# 04_-_BATTERIES_WITH_PROTECTION.net
KiCad netlist of a schematic drawn in Altium Designer
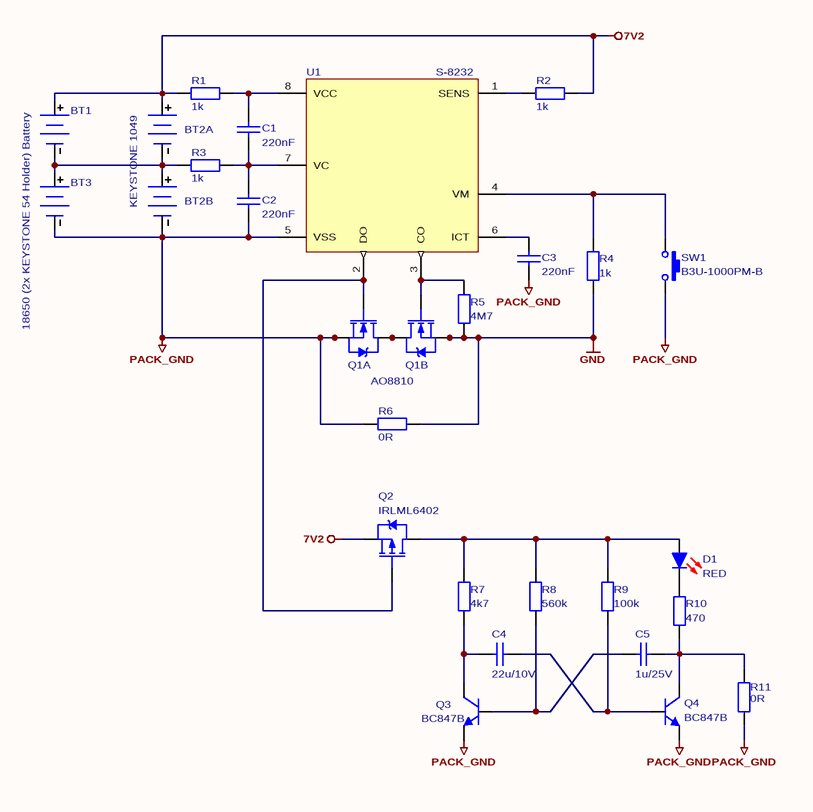
[diagram p0: [04] - BATTERIES WITH PROTECTION.SchDoc]

(export (version "E")
  (design (tool "Eeschema 10.0.6"))
  (components
    (comp (ref "BT1")
      (value "18650 (2x KEYSTONE 54 Holder) Battery")
      (footprint "KEYSTONE_54_W_18650")
      (fields (field (name "PUBLISHER") "Altium Limited"))
      (libsource (lib "baterries_and_accus") (part "18650"))
    )
    (comp (ref "BT2")
      (value "KEYSTONE 1049")
      (footprint "KEYSTONE_1049")
      (description "2x 18650 LiPo Acu in the KEYSTONE 1049 Holder")
      (libsource (lib "baterries_and_accus") (part "Keystone 1049"))
    )
    (comp (ref "BT3")
      (value "18650 (2x KEYSTONE 54 Holder) Battery")
      (footprint "KEYSTONE_54_W_18650")
      (fields (field (name "PUBLISHER") "Altium Limited"))
      (libsource (lib "baterries_and_accus") (part "18650"))
    )
    (comp (ref "C1")
      (value "220nF")
      (footprint "C0805")
      (description "Capacitor")
      (libsource (lib "capacitors") (part "Cap"))
    )
    (comp (ref "C2")
      (value "220nF")
      (footprint "C0805")
      (description "Capacitor")
      (libsource (lib "capacitors") (part "Cap"))
    )
    (comp (ref "C3")
      (value "220nF")
      (footprint "C0805")
      (description "Capacitor")
      (libsource (lib "capacitors") (part "Cap"))
    )
    (comp (ref "C4")
      (value "22u/10V")
      (footprint "C0805")
      (description "Capacitor")
      (libsource (lib "capacitors") (part "Cap"))
    )
    (comp (ref "C5")
      (value "1u/25V")
      (footprint "C0805")
      (description "Capacitor")
      (libsource (lib "capacitors") (part "Cap"))
    )
    (comp (ref "D1")
      (value "RED")
      (footprint "LED0805R")
      (description "RED LED")
      (libsource (lib "leds") (part "LED_RED"))
    )
    (comp (ref "Q1")
      (value "AO8810")
      (footprint "TSSOP8")
      (description "Dual Common Drain N-Channel MOSFET: Vds=20V, Rdson<20mR@4,5V, Id=7A")
      (libsource (lib "transistors_mos") (part "AO8810"))
    )
    (comp (ref "Q2")
      (value "IRLML6402")
      (footprint "SOT-23")
      (description "P-Channel; -20V, -3.7A, 1.3W; HEXFET Power MOS-FET")
      (libsource (lib "transistors_mos") (part "IRLML6402"))
    )
    (comp (ref "Q3")
      (value "BC847B")
      (footprint "SOT-23")
      (description "NPN General Purpose Transistor (VCE=45V, IC=100mA, HFE=200-450)")
      (libsource (lib "transistors_bjt") (part "BC847B"))
    )
    (comp (ref "Q4")
      (value "BC847B")
      (footprint "SOT-23")
      (description "NPN General Purpose Transistor (VCE=45V, IC=100mA, HFE=200-450)")
      (libsource (lib "transistors_bjt") (part "BC847B"))
    )
    (comp (ref "R1")
      (value "1k")
      (footprint "R0805")
      (description "Resistor")
      (libsource (lib "") (part "Res_1"))
    )
    (comp (ref "R2")
      (value "1k")
      (footprint "R0805")
      (description "Resistor")
      (libsource (lib "") (part "Res_1"))
    )
    (comp (ref "R3")
      (value "1k")
      (footprint "R0805")
      (description "Resistor")
      (libsource (lib "") (part "Res_1"))
    )
    (comp (ref "R4")
      (value "1k")
      (footprint "R0805")
      (description "Resistor")
      (libsource (lib "resistors") (part "Res"))
    )
    (comp (ref "R5")
      (value "4M7")
      (footprint "R0805")
      (description "Resistor")
      (libsource (lib "resistors") (part "Res"))
    )
    (comp (ref "R6")
      (value "0R")
      (footprint "R0805")
      (description "Resistor")
      (libsource (lib "") (part "Res_3"))
    )
    (comp (ref "R7")
      (value "4k7")
      (footprint "R0805")
      (description "Resistor")
      (libsource (lib "resistors") (part "Res"))
    )
    (comp (ref "R8")
      (value "560k")
      (footprint "R0805")
      (description "Resistor")
      (libsource (lib "resistors") (part "Res"))
    )
    (comp (ref "R9")
      (value "100k")
      (footprint "R0805")
      (description "Resistor")
      (libsource (lib "resistors") (part "Res"))
    )
    (comp (ref "R10")
      (value "470")
      (footprint "R0805")
      (description "Resistor")
      (libsource (lib "resistors") (part "Res"))
    )
    (comp (ref "R11")
      (value "0R")
      (footprint "R0805")
      (description "Resistor")
      (libsource (lib "") (part "Res_2"))
    )
    (comp (ref "SW1")
      (value "B3U-1000PM-B")
      (footprint "B3U-1000PM-B")
      (description "OMRON Ultra-small Tactile Switch - 12V/50mA")
      (libsource (lib "microswitches") (part "B3U-1000PM-B"))
    )
    (comp (ref "U1")
      (value "S-8232")
      (footprint "TSSOP8")
      (description "Battery Protection IC For 2-Serial-Cell Pack")
      (libsource (lib "protection_circuits") (part "S-8232"))
    )
  )
  (nets
    (net (code "1") (name "7V2") (class "Default")
      (node (ref "BT1") (pin "1") (pinfunction "+_1") (pintype "passive"))
      (node (ref "BT2") (pin "1") (pinfunction "+_1") (pintype "passive"))
      (node (ref "Q2") (pin "2") (pinfunction "S_2") (pintype "passive"))
      (node (ref "R1") (pin "1") (pinfunction "1_1") (pintype "passive"))
      (node (ref "R2") (pin "2") (pinfunction "2_2") (pintype "passive"))
    )
    (net (code "2") (name "GND") (class "Default")
      (node (ref "Q1") (pin "6") (pinfunction "S2_6") (pintype "passive"))
      (node (ref "Q1") (pin "7") (pinfunction "S2_7") (pintype "passive"))
      (node (ref "R4") (pin "2") (pinfunction "2_2") (pintype "passive"))
      (node (ref "R5") (pin "2") (pinfunction "2_2") (pintype "passive"))
      (node (ref "R6") (pin "1") (pinfunction "1_1") (pintype "passive"))
    )
    (net (code "3") (name "Net-(BT1--)") (class "Default")
      (node (ref "BT1") (pin "2") (pinfunction "-_2") (pintype "passive"))
      (node (ref "BT2") (pin "2") (pinfunction "-_2") (pintype "passive"))
      (node (ref "BT2") (pin "4") (pinfunction "+_4") (pintype "passive"))
      (node (ref "BT3") (pin "1") (pinfunction "+_1") (pintype "passive"))
      (node (ref "R3") (pin "1") (pinfunction "1_1") (pintype "passive"))
    )
    (net (code "4") (name "Net-(D1-A)") (class "Default")
      (node (ref "D1") (pin "1") (pinfunction "A_1") (pintype "passive"))
      (node (ref "Q2") (pin "3") (pinfunction "D_3") (pintype "passive"))
      (node (ref "R7") (pin "1") (pinfunction "1_1") (pintype "passive"))
      (node (ref "R8") (pin "1") (pinfunction "1_1") (pintype "passive"))
      (node (ref "R9") (pin "1") (pinfunction "1_1") (pintype "passive"))
    )
    (net (code "5") (name "Net-(D1-K)") (class "Default")
      (node (ref "D1") (pin "2") (pinfunction "K_2") (pintype "passive"))
      (node (ref "R10") (pin "1") (pinfunction "1_1") (pintype "passive"))
    )
    (net (code "6") (name "Net-(Q1A-D1{slash}D2)") (class "Default")
      (node (ref "Q1") (pin "1") (pinfunction "D1/D2_1") (pintype "passive"))
      (node (ref "Q1") (pin "8") (pinfunction "D1/D3_8") (pintype "passive"))
    )
    (net (code "7") (name "Net-(Q1A-G1)") (class "Default")
      (node (ref "Q1") (pin "4") (pinfunction "G1_4") (pintype "passive"))
      (node (ref "Q2") (pin "1") (pinfunction "G_1") (pintype "passive"))
      (node (ref "U1") (pin "2") (pinfunction "DO_2") (pintype "output"))
    )
    (net (code "8") (name "Net-(Q1B-G2)") (class "Default")
      (node (ref "Q1") (pin "5") (pinfunction "G2_5") (pintype "passive"))
      (node (ref "R5") (pin "1") (pinfunction "1_1") (pintype "passive"))
      (node (ref "U1") (pin "3") (pinfunction "CO_3") (pintype "output"))
    )
    (net (code "9") (name "Net-(Q3-B)") (class "Default")
      (node (ref "C5") (pin "1") (pinfunction "1_1") (pintype "passive"))
      (node (ref "Q3") (pin "1") (pinfunction "B_1") (pintype "passive"))
      (node (ref "R8") (pin "2") (pinfunction "2_2") (pintype "passive"))
    )
    (net (code "10") (name "Net-(Q3-C)") (class "Default")
      (node (ref "C4") (pin "1") (pinfunction "1_1") (pintype "passive"))
      (node (ref "Q3") (pin "3") (pinfunction "C_3") (pintype "passive"))
      (node (ref "R7") (pin "2") (pinfunction "2_2") (pintype "passive"))
    )
    (net (code "11") (name "Net-(Q4-B)") (class "Default")
      (node (ref "C4") (pin "2") (pinfunction "2_2") (pintype "passive"))
      (node (ref "Q4") (pin "1") (pinfunction "B_1") (pintype "passive"))
      (node (ref "R9") (pin "2") (pinfunction "2_2") (pintype "passive"))
    )
    (net (code "12") (name "Net-(Q4-C)") (class "Default")
      (node (ref "C5") (pin "2") (pinfunction "2_2") (pintype "passive"))
      (node (ref "Q4") (pin "3") (pinfunction "C_3") (pintype "passive"))
      (node (ref "R10") (pin "2") (pinfunction "2_2") (pintype "passive"))
      (node (ref "R11") (pin "2") (pinfunction "2_2") (pintype "passive"))
    )
    (net (code "13") (name "Net-(U1-ICT)") (class "Default")
      (node (ref "C3") (pin "2") (pinfunction "2_2") (pintype "passive"))
      (node (ref "U1") (pin "6") (pinfunction "ICT_6") (pintype "passive"))
    )
    (net (code "14") (name "Net-(U1-SENS)") (class "Default")
      (node (ref "R2") (pin "1") (pinfunction "1_1") (pintype "passive"))
      (node (ref "U1") (pin "1") (pinfunction "SENS_1") (pintype "passive"))
    )
    (net (code "15") (name "Net-(U1-VC)") (class "Default")
      (node (ref "C1") (pin "1") (pinfunction "1_1") (pintype "passive"))
      (node (ref "C2") (pin "2") (pinfunction "2_2") (pintype "passive"))
      (node (ref "R3") (pin "2") (pinfunction "2_2") (pintype "passive"))
      (node (ref "U1") (pin "7") (pinfunction "VC_7") (pintype "passive"))
    )
    (net (code "16") (name "Net-(U1-VCC)") (class "Default")
      (node (ref "C1") (pin "2") (pinfunction "2_2") (pintype "passive"))
      (node (ref "R1") (pin "2") (pinfunction "2_2") (pintype "passive"))
      (node (ref "U1") (pin "8") (pinfunction "VCC_8") (pintype "passive"))
    )
    (net (code "17") (name "Net-(U1-VM)") (class "Default")
      (node (ref "R4") (pin "1") (pinfunction "1_1") (pintype "passive"))
      (node (ref "SW1") (pin "1") (pinfunction "1_1") (pintype "passive"))
      (node (ref "U1") (pin "4") (pinfunction "VM_4") (pintype "passive"))
    )
    (net (code "18") (name "PACK_GND") (class "Default")
      (node (ref "BT2") (pin "3") (pinfunction "-_3") (pintype "passive"))
      (node (ref "BT3") (pin "2") (pinfunction "-_2") (pintype "passive"))
      (node (ref "C2") (pin "1") (pinfunction "1_1") (pintype "passive"))
      (node (ref "C3") (pin "1") (pinfunction "1_1") (pintype "passive"))
      (node (ref "Q1") (pin "2") (pinfunction "S1_2") (pintype "passive"))
      (node (ref "Q1") (pin "3") (pinfunction "S1_3") (pintype "passive"))
      (node (ref "Q3") (pin "2") (pinfunction "E_2") (pintype "passive"))
      (node (ref "Q4") (pin "2") (pinfunction "E_2") (pintype "passive"))
      (node (ref "R11") (pin "1") (pinfunction "1_1") (pintype "passive"))
      (node (ref "R6") (pin "2") (pinfunction "2_2") (pintype "passive"))
      (node (ref "SW1") (pin "2") (pinfunction "2_2") (pintype "passive"))
      (node (ref "U1") (pin "5") (pinfunction "VSS_5") (pintype "passive"))
    )
  )
)
